# Potencia.net
KiCad netlist of a schematic drawn in EAGLE
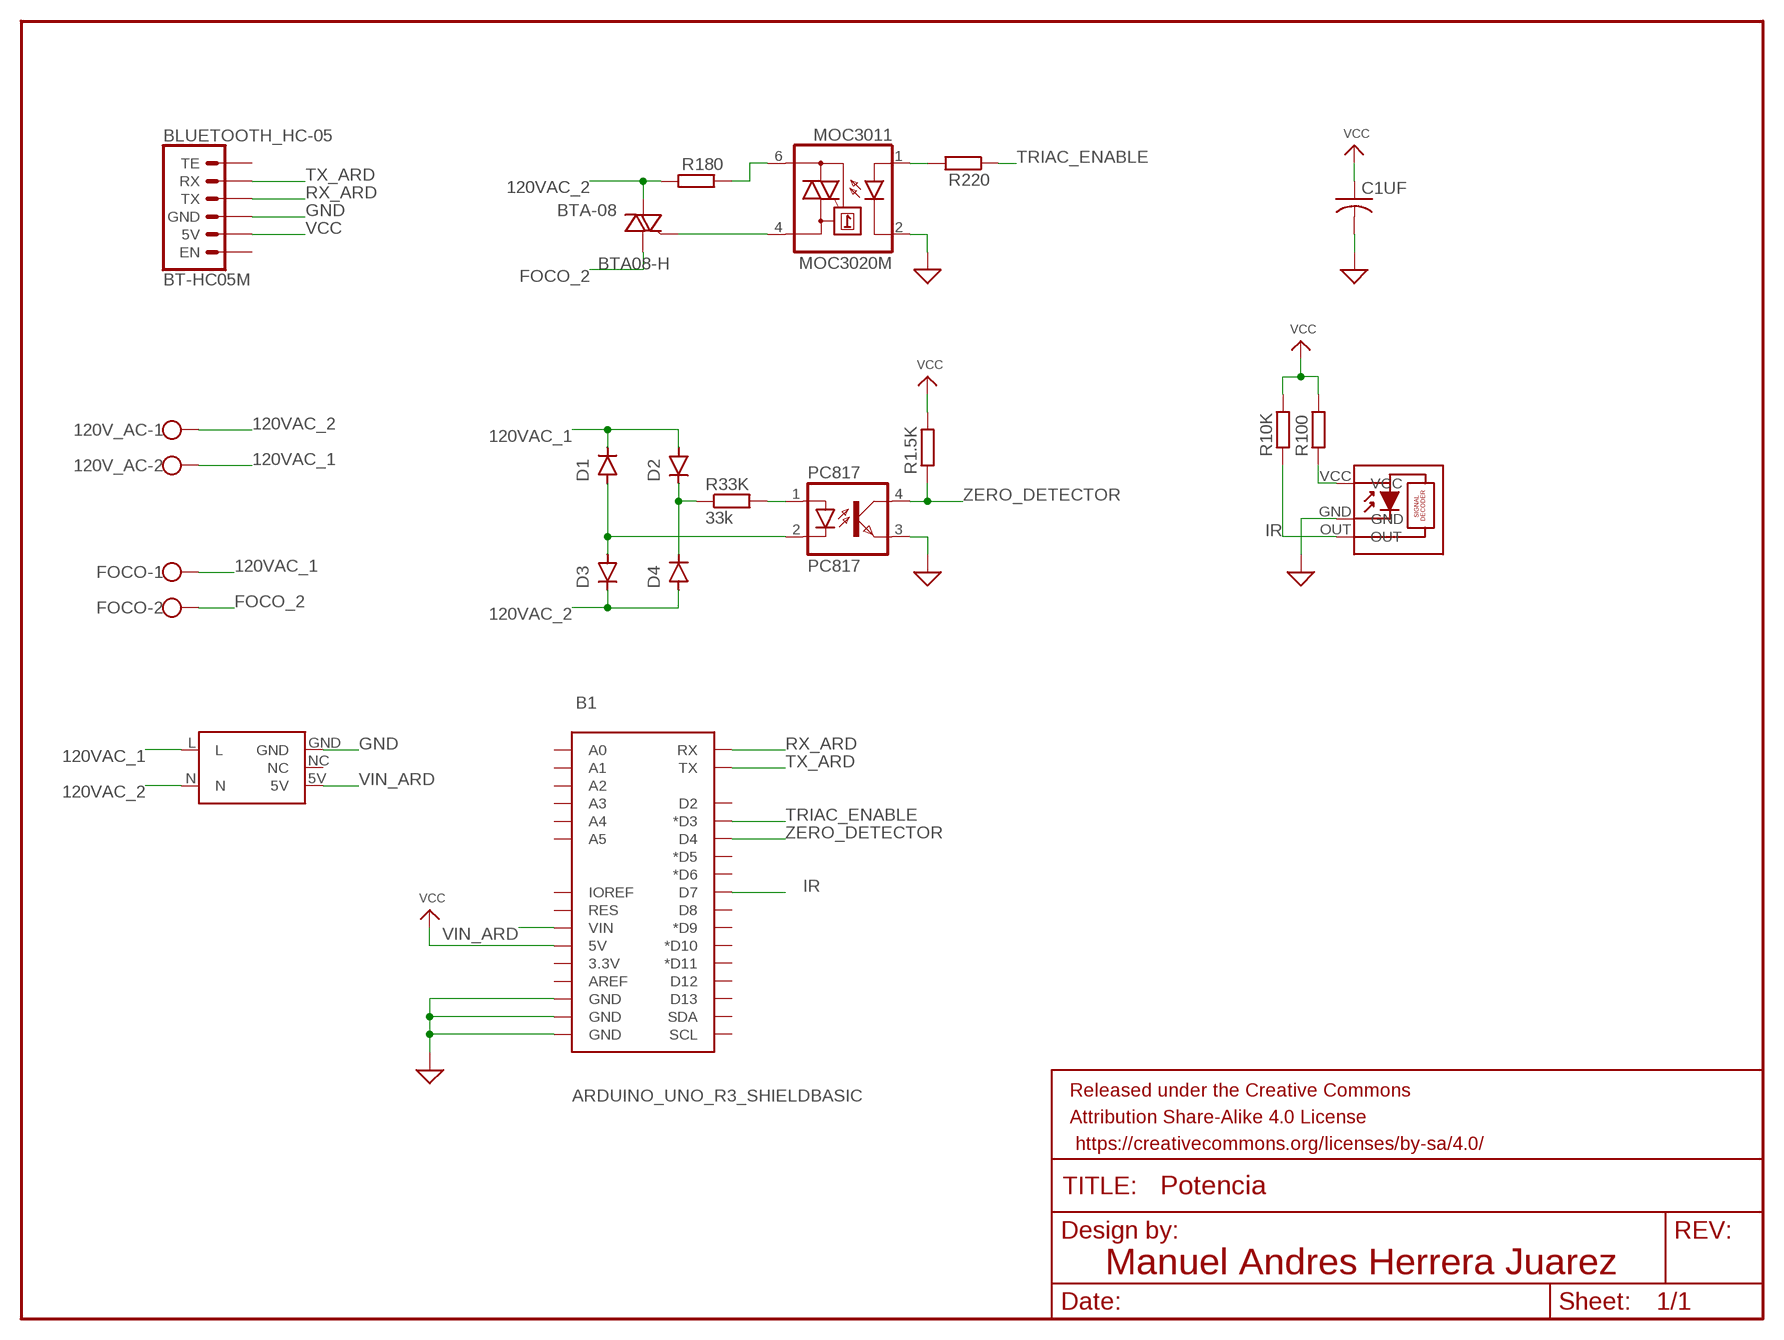
[diagram p0: schematic, sheet 1]

(export (version "E")
  (design (tool "Eeschema 10.0.6"))
  (components
    (comp (ref "120V_AC")
      (value "W237-102")
      (footprint "eagle-import:W237-102")
      (fields (field (name "MPN") "237-102"))
      (libsource (lib "eagle-import") (part "W237-102"))
    )
    (comp (ref "B1")
      (value "ARDUINO_UNO_R3_SHIELDBASIC")
      (footprint "eagle-import:UNO_R3_SHIELD")
      (libsource (lib "eagle-import") (part "ARDUINO_UNO_R3_SHIELDBASIC"))
    )
    (comp (ref "BLUETOOTH_HC-05")
      (value "BT-HC05M")
      (footprint "eagle-import:HEADER1X6")
      (libsource (lib "eagle-import") (part "BT-HC05M"))
    )
    (comp (ref "BTA-08")
      (value "BTA08-H")
      (footprint "eagle-import:TO220BH")
      (libsource (lib "eagle-import") (part "BTA08-H"))
    )
    (comp (ref "C1UF")
      (value "C-USC1206")
      (footprint "eagle-import:C1206")
      (libsource (lib "eagle-import") (part "C-USC1206"))
    )
    (comp (ref "D1")
      (value "1N4007")
      (footprint "eagle-import:DO-41")
      (fields
        (field (name "DIGIKEY_PART_NUMBER") "1N4007MSCT-ND")
        (field (name "MANUFACTURER") "Micro Commercial Co")
        (field (name "CREATED_BY") "PCBLayout.com")
      )
      (libsource (lib "eagle-import") (part "1N4007"))
    )
    (comp (ref "D2")
      (value "1N4007")
      (footprint "eagle-import:DO-41")
      (fields
        (field (name "DIGIKEY_PART_NUMBER") "1N4007MSCT-ND")
        (field (name "MANUFACTURER") "Micro Commercial Co")
        (field (name "CREATED_BY") "PCBLayout.com")
      )
      (libsource (lib "eagle-import") (part "1N4007"))
    )
    (comp (ref "D3")
      (value "1N4007")
      (footprint "eagle-import:DO-41")
      (fields
        (field (name "DIGIKEY_PART_NUMBER") "1N4007MSCT-ND")
        (field (name "MANUFACTURER") "Micro Commercial Co")
        (field (name "CREATED_BY") "PCBLayout.com")
      )
      (libsource (lib "eagle-import") (part "1N4007"))
    )
    (comp (ref "D4")
      (value "1N4007")
      (footprint "eagle-import:DO-41")
      (fields
        (field (name "DIGIKEY_PART_NUMBER") "1N4007MSCT-ND")
        (field (name "MANUFACTURER") "Micro Commercial Co")
        (field (name "CREATED_BY") "PCBLayout.com")
      )
      (libsource (lib "eagle-import") (part "1N4007"))
    )
    (comp (ref "FOCO")
      (value "W237-102")
      (footprint "eagle-import:W237-102")
      (fields (field (name "MPN") "237-102"))
      (libsource (lib "eagle-import") (part "W237-102"))
    )
    (comp (ref "FRAME2")
      (value "FRAME-LETTERNO_PACKAGE")
      (footprint "eagle-import:DUMMY")
      (fields (field (name "DESIGNER") "Nobody"))
      (libsource (lib "eagle-import") (part "FRAME-LETTERNO_PACKAGE"))
    )
    (comp (ref "IR1838")
      (value "VS138")
      (footprint "eagle-import:TO92-BCE")
      (libsource (lib "eagle-import") (part "VS138"))
    )
    (comp (ref "MOC3011")
      (value "MOC3020M")
      (footprint "eagle-import:DIL06")
      (fields (field (name "MF") "FAIRCHILD SEMICONDUCTOR") (field (name "MPN") "MOC3020-M"))
      (libsource (lib "eagle-import") (part "MOC30M20"))
    )
    (comp (ref "PC817")
      (value "PC817")
      (footprint "eagle-import:DIL04")
      (fields (field (name "MPN") "PC817X4J000F"))
      (libsource (lib "eagle-import") (part "PC817"))
    )
    (comp (ref "R1.5K")
      (value "R-EU_0207/10")
      (footprint "eagle-import:0207_10")
      (libsource (lib "eagle-import") (part "resistor_348_R-EU_0207/10"))
    )
    (comp (ref "R10K")
      (value "R-EU_0207/10")
      (footprint "eagle-import:0207_10")
      (libsource (lib "eagle-import") (part "resistor_348_R-EU_0207/10"))
    )
    (comp (ref "R33K")
      (value "33k")
      (footprint "eagle-import:0411_15")
      (libsource (lib "eagle-import") (part "resistor_348_R-EU_0411/15"))
    )
    (comp (ref "R100")
      (value "R-EU_0207/10")
      (footprint "eagle-import:0207_10")
      (libsource (lib "eagle-import") (part "resistor_348_R-EU_0207/10"))
    )
    (comp (ref "R180")
      (value "R-EU_0204/7")
      (footprint "eagle-import:0204_7")
      (libsource (lib "eagle-import") (part "R-EU_0204/7"))
    )
    (comp (ref "R220")
      (value "R-EU_0207/10")
      (footprint "eagle-import:0207_10")
      (libsource (lib "eagle-import") (part "R-EU_0207/10"))
    )
    (comp (ref "U$1")
      (value "127VAC_5VDC_CONVERTER")
      (footprint "eagle-import:127AC_5DC_CONVERTER")
      (libsource (lib "eagle-import") (part "127VAC_5VDC_CONVERTER"))
    )
  )
  (nets
    (net (code "1") (name "/120VAC_1") (class "Default")
      (node (ref "120V_AC") (pin "2") (pinfunction "KL_2") (pintype "passive"))
      (node (ref "D1") (pin "C") (pinfunction "C_C") (pintype "passive"))
      (node (ref "D2") (pin "A") (pinfunction "A_A") (pintype "passive"))
      (node (ref "FOCO") (pin "1") (pinfunction "KL_1") (pintype "passive"))
      (node (ref "U$1") (pin "L") (pinfunction "L_L") (pintype "bidirectional"))
    )
    (net (code "2") (name "/120VAC_2") (class "Default")
      (node (ref "120V_AC") (pin "1") (pinfunction "KL_1") (pintype "passive"))
      (node (ref "BTA-08") (pin "T2") (pinfunction "A2_T2") (pintype "passive"))
      (node (ref "D3") (pin "C") (pinfunction "C_C") (pintype "passive"))
      (node (ref "D4") (pin "A") (pinfunction "A_A") (pintype "passive"))
      (node (ref "R180") (pin "2") (pinfunction "2_2") (pintype "passive"))
      (node (ref "U$1") (pin "N") (pinfunction "N_N") (pintype "bidirectional"))
    )
    (net (code "3") (name "/FOCO_2") (class "Default")
      (node (ref "BTA-08") (pin "T1") (pinfunction "A1_T1") (pintype "passive"))
      (node (ref "FOCO") (pin "2") (pinfunction "KL_2") (pintype "passive"))
    )
    (net (code "4") (name "/IR") (class "Default")
      (node (ref "B1") (pin "D7") (pinfunction "D7_D7") (pintype "bidirectional"))
      (node (ref "IR1838") (pin "OUT") (pinfunction "OUT_OUT") (pintype "bidirectional"))
      (node (ref "R10K") (pin "1") (pinfunction "1_1") (pintype "passive"))
    )
    (net (code "5") (name "/RX_ARD") (class "Default")
      (node (ref "B1") (pin "RX") (pinfunction "RX_RX") (pintype "bidirectional"))
      (node (ref "BLUETOOTH_HC-05") (pin "P$3") (pinfunction "TX_P$3") (pintype "passive"))
    )
    (net (code "6") (name "/TRIAC_ENABLE") (class "Default")
      (node (ref "B1") (pin "D3") (pinfunction "*D3_D3") (pintype "bidirectional"))
      (node (ref "R220") (pin "1") (pinfunction "1_1") (pintype "passive"))
    )
    (net (code "7") (name "/TX_ARD") (class "Default")
      (node (ref "B1") (pin "TX") (pinfunction "TX_TX") (pintype "bidirectional"))
      (node (ref "BLUETOOTH_HC-05") (pin "P$2") (pinfunction "RX_P$2") (pintype "passive"))
    )
    (net (code "8") (name "/VIN_ARD") (class "Default")
      (node (ref "B1") (pin "VIN") (pinfunction "VIN_VIN") (pintype "bidirectional"))
      (node (ref "U$1") (pin "5V") (pinfunction "5V_5V") (pintype "bidirectional"))
    )
    (net (code "9") (name "/ZERO_DETECTOR") (class "Default")
      (node (ref "B1") (pin "D4") (pinfunction "D4_D4") (pintype "bidirectional"))
      (node (ref "PC817") (pin "4") (pinfunction "COL_4") (pintype "passive"))
      (node (ref "R1.5K") (pin "1") (pinfunction "1_1") (pintype "passive"))
    )
    (net (code "10") (name "Net-(D2-PadC)") (class "Default")
      (node (ref "D2") (pin "C") (pinfunction "C_C") (pintype "passive"))
      (node (ref "D4") (pin "C") (pinfunction "C_C") (pintype "passive"))
      (node (ref "R33K") (pin "1") (pinfunction "1_1") (pintype "passive"))
    )
    (net (code "11") (name "Net-(IR1838-PadVCC)") (class "Default")
      (node (ref "IR1838") (pin "VCC") (pinfunction "VCC_VCC") (pintype "bidirectional"))
      (node (ref "R100") (pin "1") (pinfunction "1_1") (pintype "passive"))
    )
    (net (code "12") (name "Net-(MOC3011-A)") (class "Default")
      (node (ref "MOC3011") (pin "1") (pinfunction "A_1") (pintype "passive"))
      (node (ref "R220") (pin "2") (pinfunction "2_2") (pintype "passive"))
    )
    (net (code "13") (name "Net-(MOC3011-A1)") (class "Default")
      (node (ref "BTA-08") (pin "G") (pinfunction "G_G") (pintype "passive"))
      (node (ref "MOC3011") (pin "4") (pinfunction "A1_4") (pintype "passive"))
    )
    (net (code "14") (name "Net-(MOC3011-A2)") (class "Default")
      (node (ref "MOC3011") (pin "6") (pinfunction "A2_6") (pintype "passive"))
      (node (ref "R180") (pin "1") (pinfunction "1_1") (pintype "passive"))
    )
    (net (code "15") (name "Net-(PC817-A)") (class "Default")
      (node (ref "PC817") (pin "1") (pinfunction "A_1") (pintype "passive"))
      (node (ref "R33K") (pin "2") (pinfunction "2_2") (pintype "passive"))
    )
    (net (code "16") (name "Net-(PC817-C)") (class "Default")
      (node (ref "D1") (pin "A") (pinfunction "A_A") (pintype "passive"))
      (node (ref "D3") (pin "A") (pinfunction "A_A") (pintype "passive"))
      (node (ref "PC817") (pin "2") (pinfunction "C_2") (pintype "passive"))
    )
    (net (code "17") (name "SUP") (class "Default")
      (node (ref "B1") (pin "GND@0") (pinfunction "GND_GND@0") (pintype "bidirectional"))
      (node (ref "B1") (pin "GND@1") (pinfunction "GND_GND@1") (pintype "bidirectional"))
      (node (ref "B1") (pin "GND@2") (pinfunction "GND_GND@2") (pintype "bidirectional"))
      (node (ref "BLUETOOTH_HC-05") (pin "P$4") (pinfunction "GND_P$4") (pintype "passive"))
      (node (ref "C1UF") (pin "2") (pinfunction "2_2") (pintype "passive"))
      (node (ref "IR1838") (pin "GND") (pinfunction "GND_GND") (pintype "bidirectional"))
      (node (ref "MOC3011") (pin "2") (pinfunction "C_2") (pintype "passive"))
      (node (ref "PC817") (pin "3") (pinfunction "EMIT_3") (pintype "passive"))
      (node (ref "U$1") (pin "GND") (pinfunction "GND_GND") (pintype "bidirectional"))
    )
    (net (code "18") (name "VCC") (class "Default")
      (node (ref "B1") (pin "5V") (pinfunction "5V_5V") (pintype "bidirectional"))
      (node (ref "BLUETOOTH_HC-05") (pin "P$5") (pinfunction "5V_P$5") (pintype "passive"))
      (node (ref "C1UF") (pin "1") (pinfunction "1_1") (pintype "passive"))
      (node (ref "R1.5K") (pin "2") (pinfunction "2_2") (pintype "passive"))
      (node (ref "R100") (pin "2") (pinfunction "2_2") (pintype "passive"))
      (node (ref "R10K") (pin "2") (pinfunction "2_2") (pintype "passive"))
    )
    (net (code "19") (name "unconnected-(B1-*D5-PadD5)") (class "Default")
      (node (ref "B1") (pin "D5") (pinfunction "*D5_D5") (pintype "bidirectional"))
    )
    (net (code "20") (name "unconnected-(B1-*D6-PadD6)") (class "Default")
      (node (ref "B1") (pin "D6") (pinfunction "*D6_D6") (pintype "bidirectional"))
    )
    (net (code "21") (name "unconnected-(B1-*D9-PadD9)") (class "Default")
      (node (ref "B1") (pin "D9") (pinfunction "*D9_D9") (pintype "bidirectional"))
    )
    (net (code "22") (name "unconnected-(B1-*D10-PadD10)") (class "Default")
      (node (ref "B1") (pin "D10") (pinfunction "*D10_D10") (pintype "bidirectional"))
    )
    (net (code "23") (name "unconnected-(B1-*D11-PadD11)") (class "Default")
      (node (ref "B1") (pin "D11") (pinfunction "*D11_D11") (pintype "bidirectional"))
    )
    (net (code "24") (name "unconnected-(B1-Pad3.3V)") (class "Default")
      (node (ref "B1") (pin "3.3V") (pinfunction "3.3V_3.3V") (pintype "bidirectional"))
    )
    (net (code "25") (name "unconnected-(B1-PadA0)") (class "Default")
      (node (ref "B1") (pin "A0") (pinfunction "A0_A0") (pintype "bidirectional"))
    )
    (net (code "26") (name "unconnected-(B1-PadA1)") (class "Default")
      (node (ref "B1") (pin "A1") (pinfunction "A1_A1") (pintype "bidirectional"))
    )
    (net (code "27") (name "unconnected-(B1-PadA2)") (class "Default")
      (node (ref "B1") (pin "A2") (pinfunction "A2_A2") (pintype "bidirectional"))
    )
    (net (code "28") (name "unconnected-(B1-PadA3)") (class "Default")
      (node (ref "B1") (pin "A3") (pinfunction "A3_A3") (pintype "bidirectional"))
    )
    (net (code "29") (name "unconnected-(B1-PadA4)") (class "Default")
      (node (ref "B1") (pin "A4") (pinfunction "A4_A4") (pintype "bidirectional"))
    )
    (net (code "30") (name "unconnected-(B1-PadA5)") (class "Default")
      (node (ref "B1") (pin "A5") (pinfunction "A5_A5") (pintype "bidirectional"))
    )
    (net (code "31") (name "unconnected-(B1-PadAREF)") (class "Default")
      (node (ref "B1") (pin "AREF") (pinfunction "AREF_AREF") (pintype "bidirectional"))
    )
    (net (code "32") (name "unconnected-(B1-PadD2)") (class "Default")
      (node (ref "B1") (pin "D2") (pinfunction "D2_D2") (pintype "bidirectional"))
    )
    (net (code "33") (name "unconnected-(B1-PadD8)") (class "Default")
      (node (ref "B1") (pin "D8") (pinfunction "D8_D8") (pintype "bidirectional"))
    )
    (net (code "34") (name "unconnected-(B1-PadD12)") (class "Default")
      (node (ref "B1") (pin "D12") (pinfunction "D12_D12") (pintype "bidirectional"))
    )
    (net (code "35") (name "unconnected-(B1-PadD13)") (class "Default")
      (node (ref "B1") (pin "D13") (pinfunction "D13_D13") (pintype "bidirectional"))
    )
    (net (code "36") (name "unconnected-(B1-PadIOREF)") (class "Default")
      (node (ref "B1") (pin "IOREF") (pinfunction "IOREF_IOREF") (pintype "bidirectional"))
    )
    (net (code "37") (name "unconnected-(B1-PadRES)") (class "Default")
      (node (ref "B1") (pin "RES") (pinfunction "RES_RES") (pintype "bidirectional"))
    )
    (net (code "38") (name "unconnected-(B1-PadSCL)") (class "Default")
      (node (ref "B1") (pin "SCL") (pinfunction "SCL_SCL") (pintype "bidirectional"))
    )
    (net (code "39") (name "unconnected-(B1-PadSDA)") (class "Default")
      (node (ref "B1") (pin "SDA") (pinfunction "SDA_SDA") (pintype "bidirectional"))
    )
    (net (code "40") (name "unconnected-(BLUETOOTH_HC-05-EN-PadP$6)") (class "Default")
      (node (ref "BLUETOOTH_HC-05") (pin "P$6") (pinfunction "EN_P$6") (pintype "passive"))
    )
    (net (code "41") (name "unconnected-(BLUETOOTH_HC-05-TE-PadP$1)") (class "Default")
      (node (ref "BLUETOOTH_HC-05") (pin "P$1") (pinfunction "TE_P$1") (pintype "passive"))
    )
    (net (code "42") (name "unconnected-(U$1-PadNC)") (class "Default")
      (node (ref "U$1") (pin "NC") (pinfunction "NC_NC") (pintype "bidirectional"))
    )
  )
)
